# WILD_USB.net
KiCad netlist of a schematic drawn in EAGLE
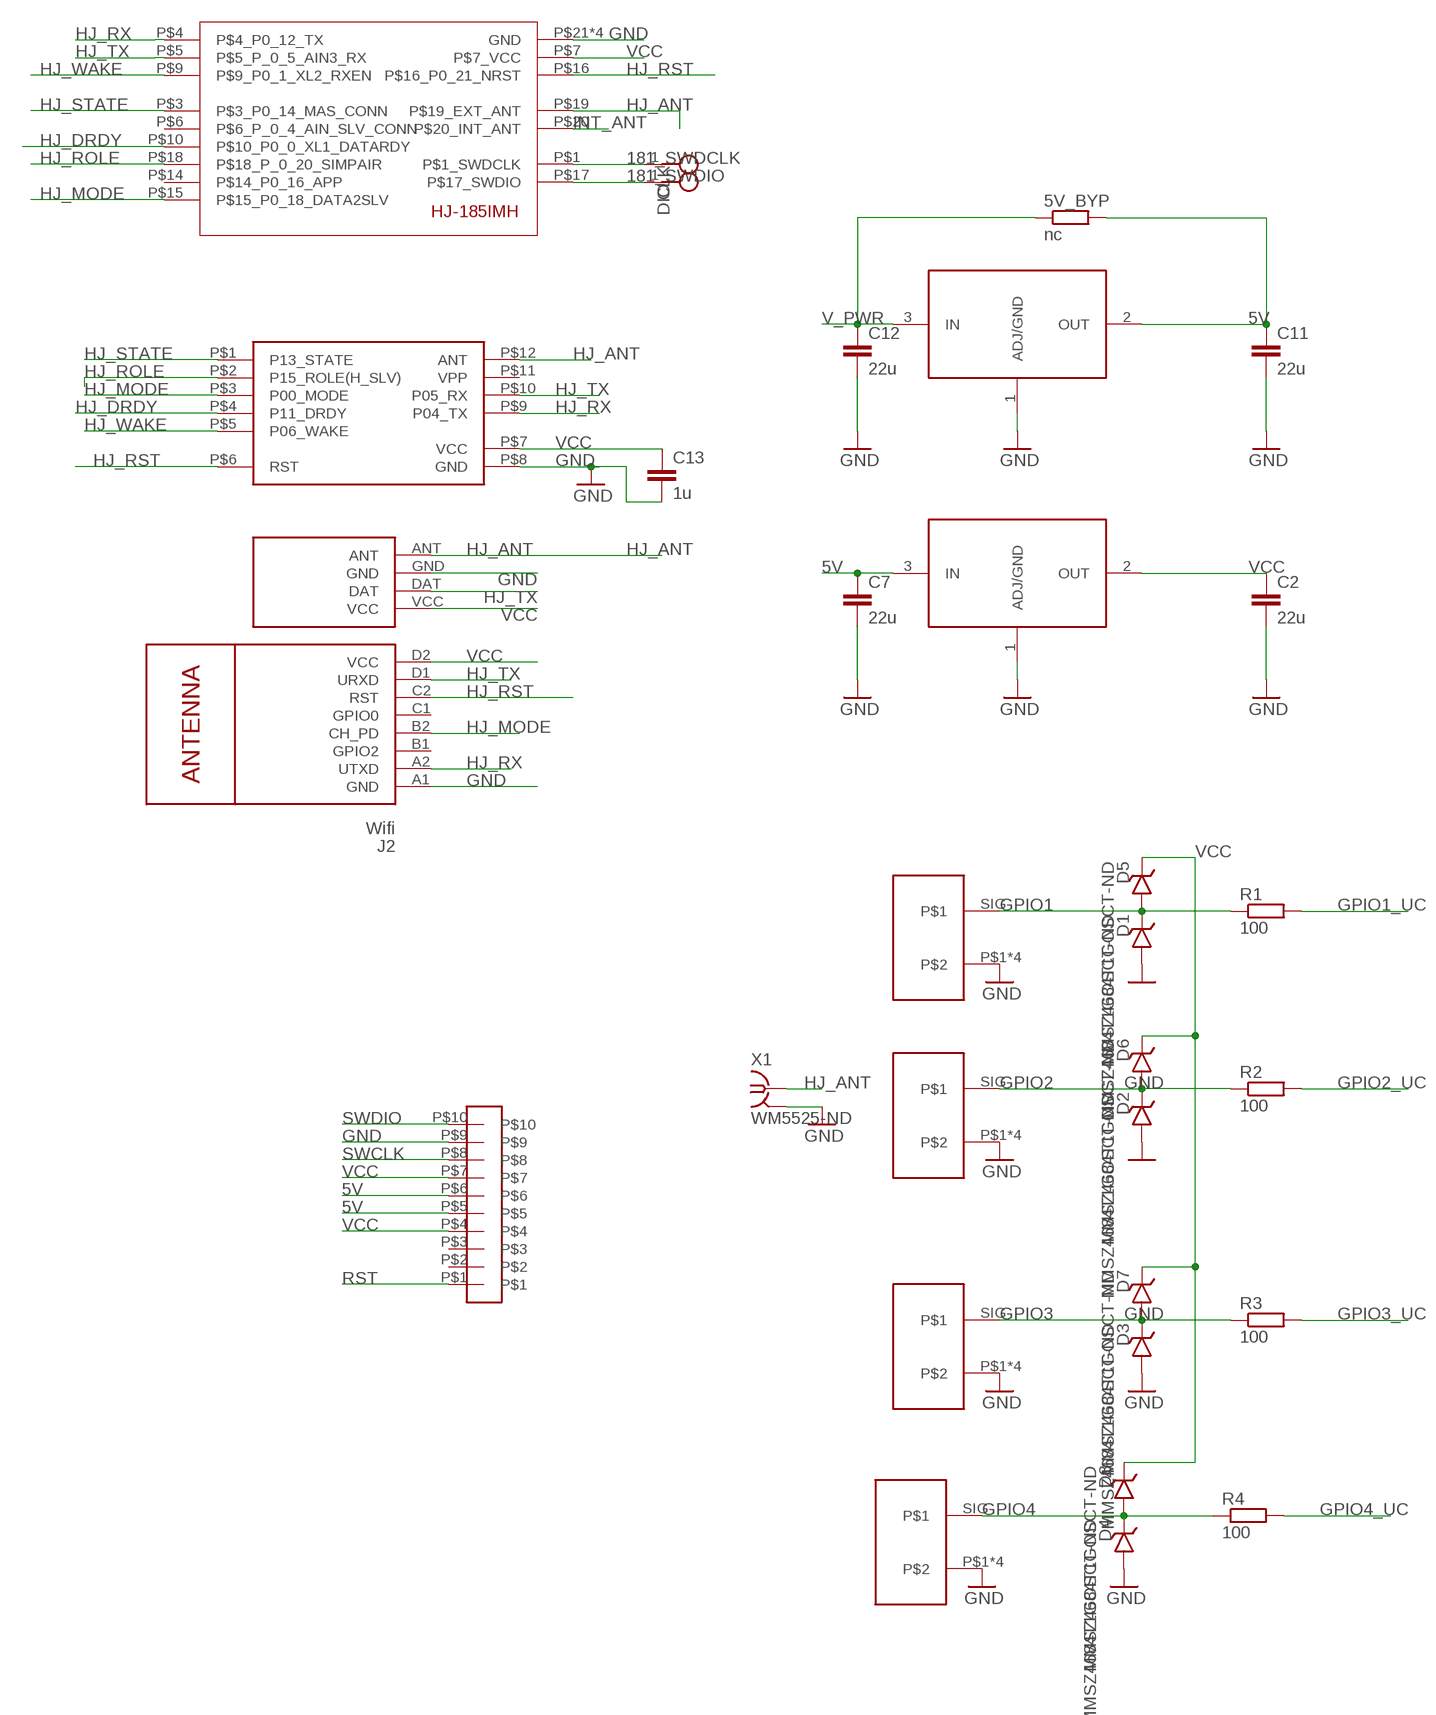
[diagram p0: schematic, sheet 1, part 1 of 2]
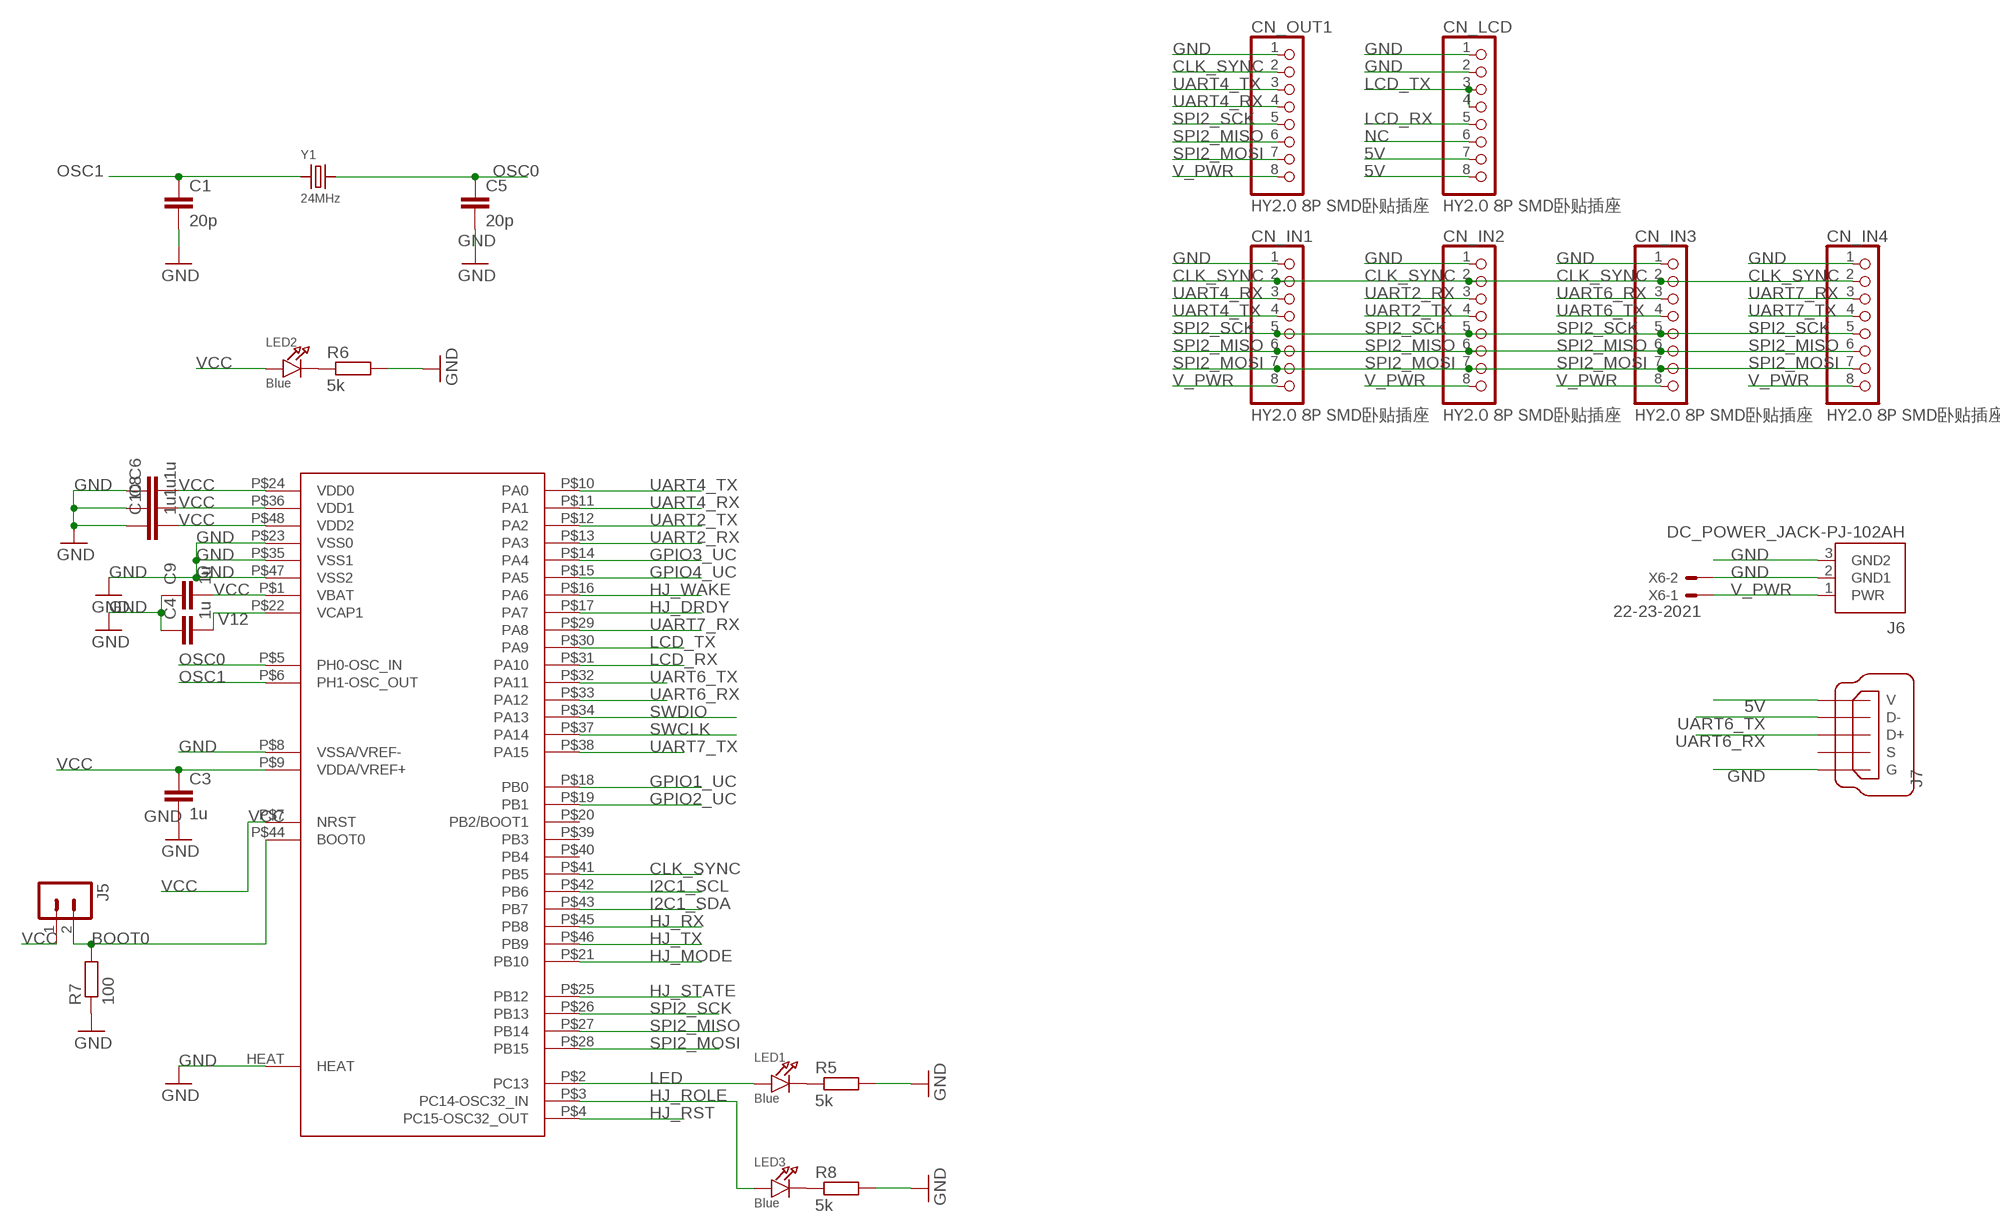
[diagram p1: schematic, sheet 1, part 2 of 2]

(export (version "E")
  (design (tool "Eeschema 10.0.6"))
  (components
    (comp (ref "5V_BYP")
      (value "nc")
      (footprint "eagle-import:R1206")
      (libsource (lib "eagle-import") (part "RR1206"))
    )
    (comp (ref "C1")
      (value "20p")
      (footprint "eagle-import:C1206")
      (libsource (lib "eagle-import") (part "CC1206"))
    )
    (comp (ref "C2")
      (value "22u")
      (footprint "eagle-import:C1206")
      (libsource (lib "eagle-import") (part "CC1206"))
    )
    (comp (ref "C3")
      (value "1u")
      (footprint "eagle-import:C1206")
      (libsource (lib "eagle-import") (part "CC1206"))
    )
    (comp (ref "C4")
      (value "1u")
      (footprint "eagle-import:C1206")
      (libsource (lib "eagle-import") (part "CC1206"))
    )
    (comp (ref "C5")
      (value "20p")
      (footprint "eagle-import:C1206")
      (libsource (lib "eagle-import") (part "CC1206"))
    )
    (comp (ref "C6")
      (value "1u")
      (footprint "eagle-import:C1206")
      (libsource (lib "eagle-import") (part "CC1206"))
    )
    (comp (ref "C7")
      (value "22u")
      (footprint "eagle-import:C1206")
      (libsource (lib "eagle-import") (part "CC1206"))
    )
    (comp (ref "C8")
      (value "1u")
      (footprint "eagle-import:C1206")
      (libsource (lib "eagle-import") (part "CC1206"))
    )
    (comp (ref "C9")
      (value "1u")
      (footprint "eagle-import:C1206")
      (libsource (lib "eagle-import") (part "CC1206"))
    )
    (comp (ref "C10")
      (value "1u")
      (footprint "eagle-import:C1206")
      (libsource (lib "eagle-import") (part "CC1206"))
    )
    (comp (ref "C11")
      (value "22u")
      (footprint "eagle-import:C1206")
      (libsource (lib "eagle-import") (part "CC1206"))
    )
    (comp (ref "C12")
      (value "22u")
      (footprint "eagle-import:C1206")
      (libsource (lib "eagle-import") (part "CC1206"))
    )
    (comp (ref "C13")
      (value "1u")
      (footprint "eagle-import:C1206")
      (libsource (lib "eagle-import") (part "CC1206"))
    )
    (comp (ref "CLK")
      (value "TESTPOINT_SMALL")
      (footprint "eagle-import:TESTPOINT_SMALL")
      (libsource (lib "eagle-import") (part "TESTPOINT_SMALL"))
    )
    (comp (ref "CN_IN1")
      (value "HY2.0 8P SMD卧贴插座")
      (footprint "eagle-import:JSTPH8")
      (libsource (lib "eagle-import") (part "JST_8PIN"))
    )
    (comp (ref "CN_IN2")
      (value "HY2.0 8P SMD卧贴插座")
      (footprint "eagle-import:JSTPH8")
      (libsource (lib "eagle-import") (part "JST_8PIN"))
    )
    (comp (ref "CN_IN3")
      (value "HY2.0 8P SMD卧贴插座")
      (footprint "eagle-import:JSTPH8")
      (libsource (lib "eagle-import") (part "JST_8PIN"))
    )
    (comp (ref "CN_IN4")
      (value "HY2.0 8P SMD卧贴插座")
      (footprint "eagle-import:JSTPH8")
      (libsource (lib "eagle-import") (part "JST_8PIN"))
    )
    (comp (ref "CN_LCD")
      (value "HY2.0 8P SMD卧贴插座")
      (footprint "eagle-import:JSTPH8")
      (libsource (lib "eagle-import") (part "JST_8PIN"))
    )
    (comp (ref "CN_OUT1")
      (value "HY2.0 8P SMD卧贴插座")
      (footprint "eagle-import:JSTPH8")
      (libsource (lib "eagle-import") (part "JST_8PIN"))
    )
    (comp (ref "D1")
      (value "MMSZ4684T1GOSCT-ND")
      (footprint "eagle-import:SOD-123")
      (libsource (lib "eagle-import") (part "DIODE_ZENER_SOD-123"))
    )
    (comp (ref "D2")
      (value "MMSZ4684T1GOSCT-ND")
      (footprint "eagle-import:SOD-123")
      (libsource (lib "eagle-import") (part "DIODE_ZENER_SOD-123"))
    )
    (comp (ref "D3")
      (value "MMSZ4684T1GOSCT-ND")
      (footprint "eagle-import:SOD-123")
      (libsource (lib "eagle-import") (part "DIODE_ZENER_SOD-123"))
    )
    (comp (ref "D4")
      (value "MMSZ4684T1GOSCT-ND")
      (footprint "eagle-import:SOD-123")
      (libsource (lib "eagle-import") (part "DIODE_ZENER_SOD-123"))
    )
    (comp (ref "D5")
      (value "MMSZ4684T1GOSCT-ND")
      (footprint "eagle-import:SOD-123")
      (libsource (lib "eagle-import") (part "DIODE_ZENER_SOD-123"))
    )
    (comp (ref "D6")
      (value "MMSZ4684T1GOSCT-ND")
      (footprint "eagle-import:SOD-123")
      (libsource (lib "eagle-import") (part "DIODE_ZENER_SOD-123"))
    )
    (comp (ref "D7")
      (value "MMSZ4684T1GOSCT-ND")
      (footprint "eagle-import:SOD-123")
      (libsource (lib "eagle-import") (part "DIODE_ZENER_SOD-123"))
    )
    (comp (ref "D8")
      (value "MMSZ4684T1GOSCT-ND")
      (footprint "eagle-import:SOD-123")
      (libsource (lib "eagle-import") (part "DIODE_ZENER_SOD-123"))
    )
    (comp (ref "DIO")
      (value "TESTPOINT_SMALL")
      (footprint "eagle-import:TESTPOINT_SMALL")
      (libsource (lib "eagle-import") (part "TESTPOINT_SMALL"))
    )
    (comp (ref "J1")
      (value "Sub-GHz")
      (footprint "eagle-import:SYN115")
      (libsource (lib "eagle-import") (part "SYN115"))
    )
    (comp (ref "J2")
      (value "Wifi")
      (footprint "eagle-import:WIRELESS-WIFI-ESP-01")
      (libsource (lib "eagle-import") (part "WIRELESS-WIFI-ESP-01"))
    )
    (comp (ref "J3")
      (value "2*5P 2.54mm 双排母 母座")
      (footprint "eagle-import:2.54MM_2X5")
      (libsource (lib "eagle-import") (part "2.54MM_2X5"))
    )
    (comp (ref "J5")
      (value "nc")
      (footprint "eagle-import:JUMPER2")
      (libsource (lib "eagle-import") (part "JUMPER2"))
    )
    (comp (ref "J6")
      (value "DC_POWER_JACK-PJ-102AH")
      (footprint "eagle-import:PJ-102AH")
      (libsource (lib "eagle-import") (part "DC_POWER_JACK-PJ-102AH"))
    )
    (comp (ref "J7")
      (value "J7")
      (footprint "eagle-import:ZX62R-B-5P")
      (libsource (lib "eagle-import") (part "MICRO-USB-ZX62R-B-5P"))
    )
    (comp (ref "LED1")
      (value "Blue")
      (footprint "eagle-import:CHIPLED_1206")
      (libsource (lib "eagle-import") (part "LED1206"))
    )
    (comp (ref "LED2")
      (value "Blue")
      (footprint "eagle-import:CHIPLED_1206")
      (libsource (lib "eagle-import") (part "LED1206"))
    )
    (comp (ref "LED3")
      (value "Blue")
      (footprint "eagle-import:CHIPLED_1206")
      (libsource (lib "eagle-import") (part "LED1206"))
    )
    (comp (ref "R1")
      (value "100")
      (footprint "eagle-import:R1206")
      (libsource (lib "eagle-import") (part "RR1206"))
    )
    (comp (ref "R2")
      (value "100")
      (footprint "eagle-import:R1206")
      (libsource (lib "eagle-import") (part "RR1206"))
    )
    (comp (ref "R3")
      (value "100")
      (footprint "eagle-import:R1206")
      (libsource (lib "eagle-import") (part "RR1206"))
    )
    (comp (ref "R4")
      (value "100")
      (footprint "eagle-import:R1206")
      (libsource (lib "eagle-import") (part "RR1206"))
    )
    (comp (ref "R5")
      (value "5k")
      (footprint "eagle-import:R1206")
      (libsource (lib "eagle-import") (part "RR1206"))
    )
    (comp (ref "R6")
      (value "5k")
      (footprint "eagle-import:R1206")
      (libsource (lib "eagle-import") (part "RR1206"))
    )
    (comp (ref "R7")
      (value "100")
      (footprint "eagle-import:R1206")
      (libsource (lib "eagle-import") (part "RR1206"))
    )
    (comp (ref "R8")
      (value "5k")
      (footprint "eagle-import:R1206")
      (libsource (lib "eagle-import") (part "RR1206"))
    )
    (comp (ref "U1")
      (value "STM32F413CHU6")
      (footprint "eagle-import:UFQFPN48")
      (libsource (lib "eagle-import") (part "STM32F411_QFN48"))
    )
    (comp (ref "U2")
      (value "HJ580")
      (footprint "eagle-import:HJ580")
      (libsource (lib "eagle-import") (part "HJ580"))
    )
    (comp (ref "U3")
      (value "HJ_185IMHQFN")
      (footprint "eagle-import:HJ_185IMH")
      (libsource (lib "eagle-import") (part "HJ_185IMHQFN"))
    )
    (comp (ref "U4")
      (value "ADP3338AKCZ-3.3")
      (footprint "eagle-import:SOT223")
      (libsource (lib "eagle-import") (part "AMS1117"))
    )
    (comp (ref "U5")
      (value "nc")
      (footprint "eagle-import:SOT223")
      (libsource (lib "eagle-import") (part "AMS1117"))
    )
    (comp (ref "X1")
      (value "WM5525-ND")
      (footprint "eagle-import:BU-SMA-H")
      (libsource (lib "eagle-import") (part "BU-SMA-H"))
    )
    (comp (ref "X2")
      (value "BNC_8MM")
      (footprint "eagle-import:BNC_V_8MM")
      (libsource (lib "eagle-import") (part "BNC_8MM"))
    )
    (comp (ref "X3")
      (value "BNC_8MM")
      (footprint "eagle-import:BNC_V_8MM")
      (libsource (lib "eagle-import") (part "BNC_8MM"))
    )
    (comp (ref "X4")
      (value "BNC_8MM")
      (footprint "eagle-import:BNC_V_8MM")
      (libsource (lib "eagle-import") (part "BNC_8MM"))
    )
    (comp (ref "X5")
      (value "BNC_8MM")
      (footprint "eagle-import:BNC_V_8MM")
      (libsource (lib "eagle-import") (part "BNC_8MM"))
    )
    (comp (ref "X6")
      (value "22-23-2021")
      (footprint "eagle-import:22-23-2021")
      (fields (field (name "MF") "MOLEX"))
      (libsource (lib "eagle-import") (part "22-23-2021"))
    )
    (comp (ref "Y1")
      (value "24MHz")
      (footprint "eagle-import:HC49UP")
      (libsource (lib "eagle-import") (part "CRYSTALSMD"))
    )
  )
  (nets
    (net (code "1") (name "/5V") (class "Default")
      (node (ref "5V_BYP") (pin "2") (pinfunction "2_2") (pintype "passive"))
      (node (ref "C11") (pin "1") (pinfunction "1_1") (pintype "passive"))
      (node (ref "C7") (pin "1") (pinfunction "1_1") (pintype "passive"))
      (node (ref "CN_LCD") (pin "7") (pinfunction "7_7") (pintype "passive"))
      (node (ref "CN_LCD") (pin "8") (pinfunction "8_8") (pintype "passive"))
      (node (ref "J3") (pin "P$5") (pinfunction "P$5_P$5") (pintype "bidirectional"))
      (node (ref "J3") (pin "P$6") (pinfunction "P$6_P$6") (pintype "bidirectional"))
      (node (ref "J7") (pin "1") (pinfunction "V_1") (pintype "input"))
      (node (ref "U4") (pin "3") (pinfunction "IN_3") (pintype "bidirectional"))
      (node (ref "U5") (pin "2") (pinfunction "OUT_2") (pintype "bidirectional"))
    )
    (net (code "2") (name "/181_SWDCLK") (class "Default")
      (node (ref "CLK") (pin "1") (pinfunction "1_1") (pintype "passive"))
      (node (ref "U3") (pin "P$1") (pinfunction "P$1_SWDCLK_P$1") (pintype "bidirectional"))
    )
    (net (code "3") (name "/181_SWDIO") (class "Default")
      (node (ref "DIO") (pin "1") (pinfunction "1_1") (pintype "passive"))
      (node (ref "U3") (pin "P$17") (pinfunction "P$17_SWDIO_P$17") (pintype "bidirectional"))
    )
    (net (code "4") (name "/BOOT0") (class "Default")
      (node (ref "J5") (pin "2") (pinfunction "2_2") (pintype "passive"))
      (node (ref "R7") (pin "2") (pinfunction "2_2") (pintype "passive"))
      (node (ref "U1") (pin "P$44") (pinfunction "BOOT0_P$44") (pintype "bidirectional"))
    )
    (net (code "5") (name "/CLK_SYNC") (class "Default")
      (node (ref "CN_IN1") (pin "2") (pinfunction "2_2") (pintype "passive"))
      (node (ref "CN_IN2") (pin "2") (pinfunction "2_2") (pintype "passive"))
      (node (ref "CN_IN3") (pin "2") (pinfunction "2_2") (pintype "passive"))
      (node (ref "CN_IN4") (pin "2") (pinfunction "2_2") (pintype "passive"))
      (node (ref "CN_OUT1") (pin "2") (pinfunction "2_2") (pintype "passive"))
      (node (ref "U1") (pin "P$41") (pinfunction "PB5_P$41") (pintype "bidirectional"))
    )
    (net (code "6") (name "/GPIO1") (class "Default")
      (node (ref "D1") (pin "1") (pinfunction "C_1") (pintype "passive"))
      (node (ref "D5") (pin "2") (pinfunction "A_2") (pintype "passive"))
      (node (ref "R1") (pin "1") (pinfunction "1_1") (pintype "passive"))
      (node (ref "X2") (pin "SIG") (pinfunction "P$1_SIG") (pintype "bidirectional"))
    )
    (net (code "7") (name "/GPIO1_UC") (class "Default")
      (node (ref "R1") (pin "2") (pinfunction "2_2") (pintype "passive"))
      (node (ref "U1") (pin "P$18") (pinfunction "PB0_P$18") (pintype "bidirectional"))
    )
    (net (code "8") (name "/GPIO2") (class "Default")
      (node (ref "D2") (pin "1") (pinfunction "C_1") (pintype "passive"))
      (node (ref "D6") (pin "2") (pinfunction "A_2") (pintype "passive"))
      (node (ref "R2") (pin "1") (pinfunction "1_1") (pintype "passive"))
      (node (ref "X3") (pin "SIG") (pinfunction "P$1_SIG") (pintype "bidirectional"))
    )
    (net (code "9") (name "/GPIO2_UC") (class "Default")
      (node (ref "R2") (pin "2") (pinfunction "2_2") (pintype "passive"))
      (node (ref "U1") (pin "P$19") (pinfunction "PB1_P$19") (pintype "bidirectional"))
    )
    (net (code "10") (name "/GPIO3") (class "Default")
      (node (ref "D3") (pin "1") (pinfunction "C_1") (pintype "passive"))
      (node (ref "D7") (pin "2") (pinfunction "A_2") (pintype "passive"))
      (node (ref "R3") (pin "1") (pinfunction "1_1") (pintype "passive"))
      (node (ref "X4") (pin "SIG") (pinfunction "P$1_SIG") (pintype "bidirectional"))
    )
    (net (code "11") (name "/GPIO3_UC") (class "Default")
      (node (ref "R3") (pin "2") (pinfunction "2_2") (pintype "passive"))
      (node (ref "U1") (pin "P$14") (pinfunction "PA4_P$14") (pintype "bidirectional"))
    )
    (net (code "12") (name "/GPIO4") (class "Default")
      (node (ref "D4") (pin "1") (pinfunction "C_1") (pintype "passive"))
      (node (ref "D8") (pin "2") (pinfunction "A_2") (pintype "passive"))
      (node (ref "R4") (pin "1") (pinfunction "1_1") (pintype "passive"))
      (node (ref "X5") (pin "SIG") (pinfunction "P$1_SIG") (pintype "bidirectional"))
    )
    (net (code "13") (name "/GPIO4_UC") (class "Default")
      (node (ref "R4") (pin "2") (pinfunction "2_2") (pintype "passive"))
      (node (ref "U1") (pin "P$15") (pinfunction "PA5_P$15") (pintype "bidirectional"))
    )
    (net (code "14") (name "/HJ_ANT") (class "Default")
      (node (ref "J1") (pin "ANT") (pinfunction "ANT_ANT") (pintype "bidirectional"))
      (node (ref "U2") (pin "P$12") (pinfunction "ANT_P$12") (pintype "bidirectional"))
      (node (ref "U3") (pin "P$19") (pinfunction "P$19_EXT_ANT_P$19") (pintype "bidirectional"))
      (node (ref "X1") (pin "1") (pinfunction "1_1") (pintype "passive"))
    )
    (net (code "15") (name "/HJ_DRDY") (class "Default")
      (node (ref "U1") (pin "P$17") (pinfunction "PA7_P$17") (pintype "bidirectional"))
      (node (ref "U2") (pin "P$4") (pinfunction "P11_DRDY_P$4") (pintype "bidirectional"))
      (node (ref "U3") (pin "P$10") (pinfunction "P$10_P0_0_XL1_DATARDY_P$10") (pintype "bidirectional"))
    )
    (net (code "16") (name "/HJ_MODE") (class "Default")
      (node (ref "J2") (pin "B2") (pinfunction "CH_PD_B2") (pintype "bidirectional"))
      (node (ref "U1") (pin "P$21") (pinfunction "PB10_P$21") (pintype "bidirectional"))
      (node (ref "U2") (pin "P$3") (pinfunction "P00_MODE_P$3") (pintype "bidirectional"))
      (node (ref "U3") (pin "P$15") (pinfunction "P$15_P0_18_DATA2SLV_P$15") (pintype "bidirectional"))
    )
    (net (code "17") (name "/HJ_ROLE") (class "Default")
      (node (ref "LED3") (pin "A") (pinfunction "A_A") (pintype "passive"))
      (node (ref "U1") (pin "P$3") (pinfunction "PC14-OSC32_IN_P$3") (pintype "bidirectional"))
      (node (ref "U2") (pin "P$2") (pinfunction "P15_ROLE(H_SLV)_P$2") (pintype "bidirectional"))
      (node (ref "U3") (pin "P$18") (pinfunction "P$18_P_0_20_SIMPAIR_P$18") (pintype "bidirectional"))
    )
    (net (code "18") (name "/HJ_RST") (class "Default")
      (node (ref "J2") (pin "C2") (pinfunction "RST_C2") (pintype "bidirectional"))
      (node (ref "U1") (pin "P$4") (pinfunction "PC15-OSC32_OUT_P$4") (pintype "bidirectional"))
      (node (ref "U2") (pin "P$6") (pinfunction "RST_P$6") (pintype "bidirectional"))
      (node (ref "U3") (pin "P$16") (pinfunction "P$16_P0_21_NRST_P$16") (pintype "bidirectional"))
    )
    (net (code "19") (name "/HJ_RX") (class "Default")
      (node (ref "J2") (pin "A2") (pinfunction "UTXD_A2") (pintype "bidirectional"))
      (node (ref "U1") (pin "P$45") (pinfunction "PB8_P$45") (pintype "bidirectional"))
      (node (ref "U2") (pin "P$9") (pinfunction "P04_TX_P$9") (pintype "bidirectional"))
      (node (ref "U3") (pin "P$4") (pinfunction "P$4_P0_12_TX_P$4") (pintype "bidirectional"))
    )
    (net (code "20") (name "/HJ_STATE") (class "Default")
      (node (ref "U1") (pin "P$25") (pinfunction "PB12_P$25") (pintype "bidirectional"))
      (node (ref "U2") (pin "P$1") (pinfunction "P13_STATE_P$1") (pintype "bidirectional"))
      (node (ref "U3") (pin "P$3") (pinfunction "P$3_P0_14_MAS_CONN_P$3") (pintype "bidirectional"))
    )
    (net (code "21") (name "/HJ_TX") (class "Default")
      (node (ref "J1") (pin "DAT") (pinfunction "DAT_DAT") (pintype "bidirectional"))
      (node (ref "J2") (pin "D1") (pinfunction "URXD_D1") (pintype "bidirectional"))
      (node (ref "U1") (pin "P$46") (pinfunction "PB9_P$46") (pintype "bidirectional"))
      (node (ref "U2") (pin "P$10") (pinfunction "P05_RX_P$10") (pintype "bidirectional"))
      (node (ref "U3") (pin "P$5") (pinfunction "P$5_P_0_5_AIN3_RX_P$5") (pintype "bidirectional"))
    )
    (net (code "22") (name "/HJ_WAKE") (class "Default")
      (node (ref "U1") (pin "P$16") (pinfunction "PA6_P$16") (pintype "bidirectional"))
      (node (ref "U2") (pin "P$5") (pinfunction "P06_WAKE_P$5") (pintype "bidirectional"))
      (node (ref "U3") (pin "P$9") (pinfunction "P$9_P0_1_XL2_RXEN_P$9") (pintype "bidirectional"))
    )
    (net (code "23") (name "/I2C1_SCL") (class "Default")
      (node (ref "U1") (pin "P$42") (pinfunction "PB6_P$42") (pintype "bidirectional"))
    )
    (net (code "24") (name "/I2C1_SDA") (class "Default")
      (node (ref "U1") (pin "P$43") (pinfunction "PB7_P$43") (pintype "bidirectional"))
    )
    (net (code "25") (name "/INT_ANT") (class "Default")
      (node (ref "U3") (pin "P$20") (pinfunction "P$20_INT_ANT_P$20") (pintype "bidirectional"))
    )
    (net (code "26") (name "/LCD_RX") (class "Default")
      (node (ref "CN_LCD") (pin "5") (pinfunction "5_5") (pintype "passive"))
      (node (ref "U1") (pin "P$31") (pinfunction "PA10_P$31") (pintype "bidirectional"))
    )
    (net (code "27") (name "/LCD_TX") (class "Default")
      (node (ref "CN_LCD") (pin "3") (pinfunction "3_3") (pintype "passive"))
      (node (ref "CN_LCD") (pin "4") (pinfunction "4_4") (pintype "passive"))
      (node (ref "U1") (pin "P$30") (pinfunction "PA9_P$30") (pintype "bidirectional"))
    )
    (net (code "28") (name "/LED") (class "Default")
      (node (ref "LED1") (pin "A") (pinfunction "A_A") (pintype "passive"))
      (node (ref "U1") (pin "P$2") (pinfunction "PC13_P$2") (pintype "bidirectional"))
    )
    (net (code "29") (name "/NC") (class "Default")
      (node (ref "CN_LCD") (pin "6") (pinfunction "6_6") (pintype "passive"))
    )
    (net (code "30") (name "/OSC0") (class "Default")
      (node (ref "C5") (pin "1") (pinfunction "1_1") (pintype "passive"))
      (node (ref "U1") (pin "P$5") (pinfunction "PH0-OSC_IN_P$5") (pintype "bidirectional"))
      (node (ref "Y1") (pin "2") (pinfunction "2_2") (pintype "passive"))
    )
    (net (code "31") (name "/OSC1") (class "Default")
      (node (ref "C1") (pin "1") (pinfunction "1_1") (pintype "passive"))
      (node (ref "U1") (pin "P$6") (pinfunction "PH1-OSC_OUT_P$6") (pintype "bidirectional"))
      (node (ref "Y1") (pin "1") (pinfunction "1_1") (pintype "passive"))
    )
    (net (code "32") (name "/RST") (class "Default")
      (node (ref "J3") (pin "P$1") (pinfunction "P$1_P$1") (pintype "bidirectional"))
    )
    (net (code "33") (name "/SPI2_MISO") (class "Default")
      (node (ref "CN_IN1") (pin "6") (pinfunction "6_6") (pintype "passive"))
      (node (ref "CN_IN2") (pin "6") (pinfunction "6_6") (pintype "passive"))
      (node (ref "CN_IN3") (pin "6") (pinfunction "6_6") (pintype "passive"))
      (node (ref "CN_IN4") (pin "6") (pinfunction "6_6") (pintype "passive"))
      (node (ref "CN_OUT1") (pin "6") (pinfunction "6_6") (pintype "passive"))
      (node (ref "U1") (pin "P$27") (pinfunction "PB14_P$27") (pintype "bidirectional"))
    )
    (net (code "34") (name "/SPI2_MOSI") (class "Default")
      (node (ref "CN_IN1") (pin "7") (pinfunction "7_7") (pintype "passive"))
      (node (ref "CN_IN2") (pin "7") (pinfunction "7_7") (pintype "passive"))
      (node (ref "CN_IN3") (pin "7") (pinfunction "7_7") (pintype "passive"))
      (node (ref "CN_IN4") (pin "7") (pinfunction "7_7") (pintype "passive"))
      (node (ref "CN_OUT1") (pin "7") (pinfunction "7_7") (pintype "passive"))
      (node (ref "U1") (pin "P$28") (pinfunction "PB15_P$28") (pintype "bidirectional"))
    )
    (net (code "35") (name "/SPI2_SCK") (class "Default")
      (node (ref "CN_IN1") (pin "5") (pinfunction "5_5") (pintype "passive"))
      (node (ref "CN_IN2") (pin "5") (pinfunction "5_5") (pintype "passive"))
      (node (ref "CN_IN3") (pin "5") (pinfunction "5_5") (pintype "passive"))
      (node (ref "CN_IN4") (pin "5") (pinfunction "5_5") (pintype "passive"))
      (node (ref "CN_OUT1") (pin "5") (pinfunction "5_5") (pintype "passive"))
      (node (ref "U1") (pin "P$26") (pinfunction "PB13_P$26") (pintype "bidirectional"))
    )
    (net (code "36") (name "/SWCLK") (class "Default")
      (node (ref "J3") (pin "P$8") (pinfunction "P$8_P$8") (pintype "bidirectional"))
      (node (ref "U1") (pin "P$37") (pinfunction "PA14_P$37") (pintype "bidirectional"))
    )
    (net (code "37") (name "/SWDIO") (class "Default")
      (node (ref "J3") (pin "P$10") (pinfunction "P$10_P$10") (pintype "bidirectional"))
      (node (ref "U1") (pin "P$34") (pinfunction "PA13_P$34") (pintype "bidirectional"))
    )
    (net (code "38") (name "/UART2_RX") (class "Default")
      (node (ref "CN_IN2") (pin "3") (pinfunction "3_3") (pintype "passive"))
      (node (ref "U1") (pin "P$13") (pinfunction "PA3_P$13") (pintype "bidirectional"))
    )
    (net (code "39") (name "/UART2_TX") (class "Default")
      (node (ref "CN_IN2") (pin "4") (pinfunction "4_4") (pintype "passive"))
      (node (ref "U1") (pin "P$12") (pinfunction "PA2_P$12") (pintype "bidirectional"))
    )
    (net (code "40") (name "/UART4_RX") (class "Default")
      (node (ref "CN_IN1") (pin "3") (pinfunction "3_3") (pintype "passive"))
      (node (ref "CN_OUT1") (pin "4") (pinfunction "4_4") (pintype "passive"))
      (node (ref "U1") (pin "P$11") (pinfunction "PA1_P$11") (pintype "bidirectional"))
    )
    (net (code "41") (name "/UART4_TX") (class "Default")
      (node (ref "CN_IN1") (pin "4") (pinfunction "4_4") (pintype "passive"))
      (node (ref "CN_OUT1") (pin "3") (pinfunction "3_3") (pintype "passive"))
      (node (ref "U1") (pin "P$10") (pinfunction "PA0_P$10") (pintype "bidirectional"))
    )
    (net (code "42") (name "/UART6_RX") (class "Default")
      (node (ref "CN_IN3") (pin "3") (pinfunction "3_3") (pintype "passive"))
      (node (ref "J7") (pin "3") (pinfunction "D+_3") (pintype "input"))
      (node (ref "U1") (pin "P$33") (pinfunction "PA12_P$33") (pintype "bidirectional"))
    )
    (net (code "43") (name "/UART6_TX") (class "Default")
      (node (ref "CN_IN3") (pin "4") (pinfunction "4_4") (pintype "passive"))
      (node (ref "J7") (pin "2") (pinfunction "D-_2") (pintype "input"))
      (node (ref "U1") (pin "P$32") (pinfunction "PA11_P$32") (pintype "bidirectional"))
    )
    (net (code "44") (name "/UART7_RX") (class "Default")
      (node (ref "CN_IN4") (pin "3") (pinfunction "3_3") (pintype "passive"))
      (node (ref "U1") (pin "P$29") (pinfunction "PA8_P$29") (pintype "bidirectional"))
    )
    (net (code "45") (name "/UART7_TX") (class "Default")
      (node (ref "CN_IN4") (pin "4") (pinfunction "4_4") (pintype "passive"))
      (node (ref "U1") (pin "P$38") (pinfunction "PA15_P$38") (pintype "bidirectional"))
    )
    (net (code "46") (name "/V12") (class "Default")
      (node (ref "C4") (pin "2") (pinfunction "2_2") (pintype "passive"))
      (node (ref "U1") (pin "P$22") (pinfunction "VCAP1_P$22") (pintype "bidirectional"))
    )
    (net (code "47") (name "/VCC") (class "Default")
      (node (ref "C10") (pin "2") (pinfunction "2_2") (pintype "passive"))
      (node (ref "C13") (pin "1") (pinfunction "1_1") (pintype "passive"))
      (node (ref "C2") (pin "1") (pinfunction "1_1") (pintype "passive"))
      (node (ref "C3") (pin "1") (pinfunction "1_1") (pintype "passive"))
      (node (ref "C6") (pin "2") (pinfunction "2_2") (pintype "passive"))
      (node (ref "C8") (pin "2") (pinfunction "2_2") (pintype "passive"))
      (node (ref "C9") (pin "2") (pinfunction "2_2") (pintype "passive"))
      (node (ref "D5") (pin "1") (pinfunction "C_1") (pintype "passive"))
      (node (ref "D6") (pin "1") (pinfunction "C_1") (pintype "passive"))
      (node (ref "D7") (pin "1") (pinfunction "C_1") (pintype "passive"))
      (node (ref "D8") (pin "1") (pinfunction "C_1") (pintype "passive"))
      (node (ref "J1") (pin "VCC") (pinfunction "VCC_VCC") (pintype "bidirectional"))
      (node (ref "J2") (pin "D2") (pinfunction "VCC_D2") (pintype "power_in"))
      (node (ref "J3") (pin "P$4") (pinfunction "P$4_P$4") (pintype "bidirectional"))
      (node (ref "J3") (pin "P$7") (pinfunction "P$7_P$7") (pintype "bidirectional"))
      (node (ref "J5") (pin "1") (pinfunction "1_1") (pintype "passive"))
      (node (ref "LED2") (pin "A") (pinfunction "A_A") (pintype "passive"))
      (node (ref "U1") (pin "P$1") (pinfunction "VBAT_P$1") (pintype "bidirectional"))
      (node (ref "U1") (pin "P$24") (pinfunction "VDD0_P$24") (pintype "bidirectional"))
      (node (ref "U1") (pin "P$36") (pinfunction "VDD1_P$36") (pintype "bidirectional"))
      (node (ref "U1") (pin "P$48") (pinfunction "VDD2_P$48") (pintype "bidirectional"))
      (node (ref "U1") (pin "P$7") (pinfunction "NRST_P$7") (pintype "bidirectional"))
      (node (ref "U1") (pin "P$9") (pinfunction "VDDA/VREF+_P$9") (pintype "bidirectional"))
      (node (ref "U2") (pin "P$7") (pinfunction "VCC_P$7") (pintype "bidirectional"))
      (node (ref "U3") (pin "P$7") (pinfunction "P$7_VCC_P$7") (pintype "bidirectional"))
      (node (ref "U4") (pin "2") (pinfunction "OUT_2") (pintype "bidirectional"))
    )
    (net (code "48") (name "/V_PWR") (class "Default")
      (node (ref "5V_BYP") (pin "1") (pinfunction "1_1") (pintype "passive"))
      (node (ref "C12") (pin "1") (pinfunction "1_1") (pintype "passive"))
      (node (ref "CN_IN1") (pin "8") (pinfunction "8_8") (pintype "passive"))
      (node (ref "CN_IN2") (pin "8") (pinfunction "8_8") (pintype "passive"))
      (node (ref "CN_IN3") (pin "8") (pinfunction "8_8") (pintype "passive"))
      (node (ref "CN_IN4") (pin "8") (pinfunction "8_8") (pintype "passive"))
      (node (ref "CN_OUT1") (pin "8") (pinfunction "8_8") (pintype "passive"))
      (node (ref "J6") (pin "1") (pinfunction "PWR_1") (pintype "power_in"))
      (node (ref "U5") (pin "3") (pinfunction "IN_3") (pintype "bidirectional"))
      (node (ref "X6") (pin "1") (pinfunction "S_1") (pintype "passive"))
    )
    (net (code "49") (name "GND") (class "Default")
      (node (ref "C1") (pin "2") (pinfunction "2_2") (pintype "passive"))
      (node (ref "C10") (pin "1") (pinfunction "1_1") (pintype "passive"))
      (node (ref "C11") (pin "2") (pinfunction "2_2") (pintype "passive"))
      (node (ref "C12") (pin "2") (pinfunction "2_2") (pintype "passive"))
      (node (ref "C13") (pin "2") (pinfunction "2_2") (pintype "passive"))
      (node (ref "C2") (pin "2") (pinfunction "2_2") (pintype "passive"))
      (node (ref "C3") (pin "2") (pinfunction "2_2") (pintype "passive"))
      (node (ref "C4") (pin "1") (pinfunction "1_1") (pintype "passive"))
      (node (ref "C5") (pin "2") (pinfunction "2_2") (pintype "passive"))
      (node (ref "C6") (pin "1") (pinfunction "1_1") (pintype "passive"))
      (node (ref "C7") (pin "2") (pinfunction "2_2") (pintype "passive"))
      (node (ref "C8") (pin "1") (pinfunction "1_1") (pintype "passive"))
      (node (ref "C9") (pin "1") (pinfunction "1_1") (pintype "passive"))
      (node (ref "CN_IN1") (pin "1") (pinfunction "1_1") (pintype "passive"))
      (node (ref "CN_IN2") (pin "1") (pinfunction "1_1") (pintype "passive"))
      (node (ref "CN_IN3") (pin "1") (pinfunction "1_1") (pintype "passive"))
      (node (ref "CN_IN4") (pin "1") (pinfunction "1_1") (pintype "passive"))
      (node (ref "CN_LCD") (pin "1") (pinfunction "1_1") (pintype "passive"))
      (node (ref "CN_LCD") (pin "2") (pinfunction "2_2") (pintype "passive"))
      (node (ref "CN_OUT1") (pin "1") (pinfunction "1_1") (pintype "passive"))
      (node (ref "D1") (pin "2") (pinfunction "A_2") (pintype "passive"))
      (node (ref "D2") (pin "2") (pinfunction "A_2") (pintype "passive"))
      (node (ref "D3") (pin "2") (pinfunction "A_2") (pintype "passive"))
      (node (ref "D4") (pin "2") (pinfunction "A_2") (pintype "passive"))
      (node (ref "J1") (pin "GND") (pinfunction "GND_GND") (pintype "bidirectional"))
      (node (ref "J2") (pin "A1") (pinfunction "GND_A1") (pintype "power_in"))
      (node (ref "J3") (pin "P$9") (pinfunction "P$9_P$9") (pintype "bidirectional"))
      (node (ref "J6") (pin "2") (pinfunction "GND1_2") (pintype "power_in"))
      (node (ref "J6") (pin "3") (pinfunction "GND2_3") (pintype "power_in"))
      (node (ref "J7") (pin "5") (pinfunction "G_5") (pintype "input"))
      (node (ref "R5") (pin "2") (pinfunction "2_2") (pintype "passive"))
      (node (ref "R6") (pin "2") (pinfunction "2_2") (pintype "passive"))
      (node (ref "R7") (pin "1") (pinfunction "1_1") (pintype "passive"))
      (node (ref "R8") (pin "2") (pinfunction "2_2") (pintype "passive"))
      (node (ref "U1") (pin "HEAT") (pinfunction "HEAT_HEAT") (pintype "bidirectional"))
      (node (ref "U1") (pin "P$23") (pinfunction "VSS0_P$23") (pintype "bidirectional"))
      (node (ref "U1") (pin "P$35") (pinfunction "VSS1_P$35") (pintype "bidirectional"))
      (node (ref "U1") (pin "P$47") (pinfunction "VSS2_P$47") (pintype "bidirectional"))
      (node (ref "U1") (pin "P$8") (pinfunction "VSSA/VREF-_P$8") (pintype "bidirectional"))
      (node (ref "U2") (pin "P$8") (pinfunction "GND_P$8") (pintype "bidirectional"))
      (node (ref "U3") (pin "P$21") (pinfunction "GND_P$21") (pintype "bidirectional"))
      (node (ref "U3") (pin "P$22") (pinfunction "GND_P$22") (pintype "bidirectional"))
      (node (ref "U3") (pin "P$23") (pinfunction "GND_P$23") (pintype "bidirectional"))
      (node (ref "U3") (pin "P$24") (pinfunction "GND_P$24") (pintype "bidirectional"))
      (node (ref "U4") (pin "1") (pinfunction "ADJ/GND_1") (pintype "bidirectional"))
      (node (ref "U5") (pin "1") (pinfunction "ADJ/GND_1") (pintype "bidirectional"))
      (node (ref "X1") (pin "2") (pinfunction "2_2") (pintype "passive"))
      (node (ref "X1") (pin "3") (pinfunction "2_3") (pintype "passive"))
      (node (ref "X1") (pin "4") (pinfunction "2_4") (pintype "passive"))
      (node (ref "X1") (pin "5") (pinfunction "2_5") (pintype "passive"))
      (node (ref "X2") (pin "P$1") (pinfunction "P$2_P$1") (pintype "bidirectional"))
      (node (ref "X2") (pin "P$2") (pinfunction "P$2_P$2") (pintype "bidirectional"))
      (node (ref "X2") (pin "P$3") (pinfunction "P$2_P$3") (pintype "bidirectional"))
      (node (ref "X2") (pin "P$4") (pinfunction "P$2_P$4") (pintype "bidirectional"))
      (node (ref "X3") (pin "P$1") (pinfunction "P$2_P$1") (pintype "bidirectional"))
      (node (ref "X3") (pin "P$2") (pinfunction "P$2_P$2") (pintype "bidirectional"))
      (node (ref "X3") (pin "P$3") (pinfunction "P$2_P$3") (pintype "bidirectional"))
      (node (ref "X3") (pin "P$4") (pinfunction "P$2_P$4") (pintype "bidirectional"))
      (node (ref "X4") (pin "P$1") (pinfunction "P$2_P$1") (pintype "bidirectional"))
      (node (ref "X4") (pin "P$2") (pinfunction "P$2_P$2") (pintype "bidirectional"))
      (node (ref "X4") (pin "P$3") (pinfunction "P$2_P$3") (pintype "bidirectional"))
      (node (ref "X4") (pin "P$4") (pinfunction "P$2_P$4") (pintype "bidirectional"))
      (node (ref "X5") (pin "P$1") (pinfunction "P$2_P$1") (pintype "bidirectional"))
      (node (ref "X5") (pin "P$2") (pinfunction "P$2_P$2") (pintype "bidirectional"))
      (node (ref "X5") (pin "P$3") (pinfunction "P$2_P$3") (pintype "bidirectional"))
      (node (ref "X5") (pin "P$4") (pinfunction "P$2_P$4") (pintype "bidirectional"))
      (node (ref "X6") (pin "2") (pinfunction "S_2") (pintype "passive"))
    )
    (net (code "50") (name "Net-(LED1-PadC)") (class "Default")
      (node (ref "LED1") (pin "C") (pinfunction "C_C") (pintype "passive"))
      (node (ref "R5") (pin "1") (pinfunction "1_1") (pintype "passive"))
    )
    (net (code "51") (name "Net-(LED2-PadC)") (class "Default")
      (node (ref "LED2") (pin "C") (pinfunction "C_C") (pintype "passive"))
      (node (ref "R6") (pin "1") (pinfunction "1_1") (pintype "passive"))
    )
    (net (code "52") (name "Net-(LED3-PadC)") (class "Default")
      (node (ref "LED3") (pin "C") (pinfunction "C_C") (pintype "passive"))
      (node (ref "R8") (pin "1") (pinfunction "1_1") (pintype "passive"))
    )
    (net (code "53") (name "unconnected-(J2-GPIO0-PadC1)") (class "Default")
      (node (ref "J2") (pin "C1") (pinfunction "GPIO0_C1") (pintype "bidirectional"))
    )
    (net (code "54") (name "unconnected-(J2-GPIO2-PadB1)") (class "Default")
      (node (ref "J2") (pin "B1") (pinfunction "GPIO2_B1") (pintype "bidirectional"))
    )
    (net (code "55") (name "unconnected-(J3-PadP$2)") (class "Default")
      (node (ref "J3") (pin "P$2") (pinfunction "P$2_P$2") (pintype "bidirectional"))
    )
    (net (code "56") (name "unconnected-(J3-PadP$3)") (class "Default")
      (node (ref "J3") (pin "P$3") (pinfunction "P$3_P$3") (pintype "bidirectional"))
    )
    (net (code "57") (name "unconnected-(J7A-S-Pad4)") (class "Default")
      (node (ref "J7") (pin "4") (pinfunction "S_4") (pintype "input"))
    )
    (net (code "58") (name "unconnected-(U1-PB2{slash}BOOT1-PadP$20)") (class "Default")
      (node (ref "U1") (pin "P$20") (pinfunction "PB2/BOOT1_P$20") (pintype "bidirectional"))
    )
    (net (code "59") (name "unconnected-(U1-PB3-PadP$39)") (class "Default")
      (node (ref "U1") (pin "P$39") (pinfunction "PB3_P$39") (pintype "bidirectional"))
    )
    (net (code "60") (name "unconnected-(U1-PB4-PadP$40)") (class "Default")
      (node (ref "U1") (pin "P$40") (pinfunction "PB4_P$40") (pintype "bidirectional"))
    )
    (net (code "61") (name "unconnected-(U2-VPP-PadP$11)") (class "Default")
      (node (ref "U2") (pin "P$11") (pinfunction "VPP_P$11") (pintype "bidirectional"))
    )
    (net (code "62") (name "unconnected-(U3-P$6_P_0_4_AIN_SLV_CONN-PadP$6)") (class "Default")
      (node (ref "U3") (pin "P$6") (pinfunction "P$6_P_0_4_AIN_SLV_CONN_P$6") (pintype "bidirectional"))
    )
    (net (code "63") (name "unconnected-(U3-P$14_P0_16_APP-PadP$14)") (class "Default")
      (node (ref "U3") (pin "P$14") (pinfunction "P$14_P0_16_APP_P$14") (pintype "bidirectional"))
    )
  )
)
